# MX25R3235F.net
KiCad netlist of a schematic drawn in EAGLE
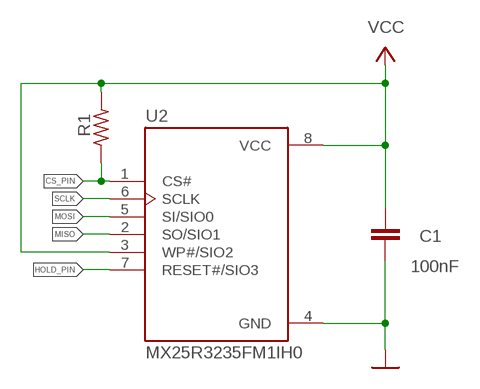
[diagram p0: schematic, sheet 1]

(export (version "E")
  (design (tool "Eeschema 10.0.6"))
  (components
    (comp (ref "C1")
      (value "100nF")
      (footprint "eagle-import:C0603")
      (libsource (lib "eagle-import") (part "C-EUC0603"))
    )
    (comp (ref "R1")
      (value "R-US_R0603")
      (footprint "eagle-import:R0603")
      (libsource (lib "eagle-import") (part "R-US_R0603"))
    )
    (comp (ref "U2")
      (value "MX25R3235FM1IH0")
      (footprint "eagle-import:SOIC127P600X175-8N")
      (fields (field (name "MF") "Macronix"))
      (libsource (lib "eagle-import") (part "MX25R3235FM1IH0"))
    )
  )
  (nets
    (net (code "1") (name "CS_PIN") (class "Default")
      (node (ref "R1") (pin "1") (pinfunction "1_1") (pintype "passive"))
      (node (ref "U2") (pin "1") (pinfunction "CS#_1") (pintype "input"))
    )
    (net (code "2") (name "GND") (class "Default")
      (node (ref "C1") (pin "1") (pinfunction "1_1") (pintype "passive"))
      (node (ref "U2") (pin "4") (pinfunction "GND_4") (pintype "power_in"))
    )
    (net (code "3") (name "HOLD_PIN") (class "Default")
      (node (ref "U2") (pin "7") (pinfunction "RESET#/SIO3_7") (pintype "bidirectional"))
    )
    (net (code "4") (name "MISO") (class "Default")
      (node (ref "U2") (pin "2") (pinfunction "SO/SIO1_2") (pintype "bidirectional"))
    )
    (net (code "5") (name "MOSI") (class "Default")
      (node (ref "U2") (pin "5") (pinfunction "SI/SIO0_5") (pintype "bidirectional"))
    )
    (net (code "6") (name "SCLK") (class "Default")
      (node (ref "U2") (pin "6") (pinfunction "SCLK_6") (pintype "input"))
    )
    (net (code "7") (name "VCC") (class "Default")
      (node (ref "C1") (pin "2") (pinfunction "2_2") (pintype "passive"))
      (node (ref "R1") (pin "2") (pinfunction "2_2") (pintype "passive"))
      (node (ref "U2") (pin "3") (pinfunction "WP#/SIO2_3") (pintype "bidirectional"))
      (node (ref "U2") (pin "8") (pinfunction "VCC_8") (pintype "power_in"))
    )
  )
)
